# sch_AGV_Power.net
KiCad netlist of a schematic drawn in Altium Designer
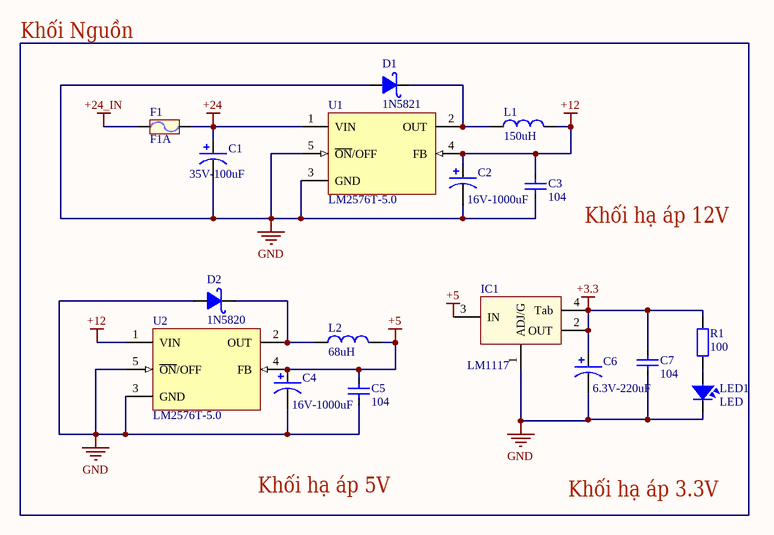
[diagram p0: sch_AGV_Power.SchDoc]

(export (version "E")
  (design (tool "Eeschema 10.0.6"))
  (components
    (comp (ref "C1")
      (value "35V-100uF")
      (footprint "CAP_D6.3")
      (description "Polarized Capacitor (Axial)")
      (fields (field (name "PUBLISHER") "Altium Limited"))
      (libsource (lib "schelib_AGVcontrol") (part "CapPol"))
    )
    (comp (ref "C2")
      (value "16V-1000uF")
      (footprint "CAP_D10")
      (description "Polarized Capacitor (Axial)")
      (fields (field (name "PUBLISHER") "Altium Limited"))
      (libsource (lib "schelib_AGVcontrol") (part "CapPol"))
    )
    (comp (ref "C3")
      (value "104")
      (footprint "CAP_0805")
      (description "Capacitor")
      (fields (field (name "PUBLISHER") "Altium Limited"))
      (libsource (lib "schelib_AGVcontrol") (part "CapSMD"))
    )
    (comp (ref "C4")
      (value "16V-1000uF")
      (footprint "CAP_D10")
      (description "Polarized Capacitor (Axial)")
      (fields (field (name "PUBLISHER") "Altium Limited"))
      (libsource (lib "schelib_AGVcontrol") (part "CapPol"))
    )
    (comp (ref "C5")
      (value "104")
      (footprint "CAP_0805")
      (description "Capacitor")
      (fields (field (name "PUBLISHER") "Altium Limited"))
      (libsource (lib "schelib_AGVcontrol") (part "CapSMD"))
    )
    (comp (ref "C6")
      (value "6.3V-220uF")
      (footprint "CAP_D10")
      (description "Polarized Capacitor (Axial)")
      (fields (field (name "PUBLISHER") "Altium Limited"))
      (libsource (lib "schelib_AGVcontrol") (part "CapPol"))
    )
    (comp (ref "C7")
      (value "104")
      (footprint "CAP_0805")
      (description "Capacitor")
      (fields (field (name "PUBLISHER") "Altium Limited"))
      (libsource (lib "schelib_AGVcontrol") (part "CapSMD"))
    )
    (comp (ref "D1")
      (value "1N5821")
      (footprint "SMA")
      (description "Schottky Rectifiers")
      (libsource (lib "schelib_AGVcontrol") (part "1N5822"))
    )
    (comp (ref "D2")
      (value "1N5820")
      (footprint "SMA")
      (description "Schottky Rectifiers")
      (libsource (lib "schelib_AGVcontrol") (part "1N5822"))
    )
    (comp (ref "F1")
      (value "F1A")
      (footprint "FUSE")
      (description "Fuse")
      (fields (field (name "DESIGNED BY") "VanDungEvn"))
      (libsource (lib "schelib_AGVcontrol") (part "Fuse"))
    )
    (comp (ref "IC1")
      (value "LM1117")
      (footprint "SOT223-4N")
      (description "3v3")
      (libsource (lib "schelib_AGVcontrol") (part "LM1117"))
    )
    (comp (ref "L1")
      (value "150uH")
      (footprint "L-SMD-M-12x10")
      (description "Inductor")
      (libsource (lib "schelib_AGVcontrol") (part "Inductor"))
    )
    (comp (ref "L2")
      (value "68uH")
      (footprint "L-SMD-M-12x10")
      (description "Inductor")
      (libsource (lib "schelib_AGVcontrol") (part "Inductor"))
    )
    (comp (ref "LED1")
      (value "LED")
      (footprint "LED_BLUE_SMD_0805")
      (description "LED Single colour Green and Red")
      (libsource (lib "schelib_AGVcontrol") (part "LED"))
    )
    (comp (ref "R1")
      (value "100")
      (footprint "RES_SMD_0805")
      (description "Resistor")
      (fields
        (field (name "MANUFACTURER") "Generic Components")
        (field (name "PUBLISHER") "Altium Hobart Technology Centre")
      )
      (libsource (lib "schelib_AGVcontrol") (part "Res"))
    )
    (comp (ref "U1")
      (value "LM2576T-5.0")
      (footprint "TO-263")
      (description "SIMPLE SWITCHER; 3A Step-Down Voltage Regulator")
      (fields
        (field (name "MANUFACTURER") "National Semiconductor")
        (field (name "DIGIKEYPARTNUMBER") "LM2576T-5.0-ND")
        (field (name "PUBLISHER") "Altium Limited")
      )
      (libsource (lib "schelib_AGVcontrol") (part "LM2576T-5.0"))
    )
    (comp (ref "U2")
      (value "LM2576T-5.0")
      (footprint "TO-263")
      (description "SIMPLE SWITCHER; 3A Step-Down Voltage Regulator")
      (fields
        (field (name "MANUFACTURER") "National Semiconductor")
        (field (name "DIGIKEYPARTNUMBER") "LM2576T-5.0-ND")
        (field (name "PUBLISHER") "Altium Limited")
      )
      (libsource (lib "schelib_AGVcontrol") (part "LM2576T-5.0"))
    )
  )
  (nets
    (net (code "1") (name "+3.3") (class "Default")
      (node (ref "C6") (pin "1") (pinfunction "1_1") (pintype "passive"))
      (node (ref "C7") (pin "2") (pinfunction "2_2") (pintype "passive"))
      (node (ref "IC1") (pin "2") (pinfunction "OUT_2") (pintype "passive"))
      (node (ref "IC1") (pin "4") (pinfunction "Tab_4") (pintype "passive"))
      (node (ref "R1") (pin "1") (pinfunction "1_1") (pintype "passive"))
    )
    (net (code "2") (name "+5") (class "Default")
      (node (ref "C4") (pin "1") (pinfunction "1_1") (pintype "passive"))
      (node (ref "C5") (pin "2") (pinfunction "2_2") (pintype "passive"))
      (node (ref "IC1") (pin "3") (pinfunction "IN_3") (pintype "passive"))
      (node (ref "L2") (pin "2") (pinfunction "2_2") (pintype "passive"))
      (node (ref "U2") (pin "4") (pinfunction "FB_4") (pintype "input"))
    )
    (net (code "3") (name "+12") (class "Default")
      (node (ref "C2") (pin "1") (pinfunction "1_1") (pintype "passive"))
      (node (ref "C3") (pin "2") (pinfunction "2_2") (pintype "passive"))
      (node (ref "L1") (pin "2") (pinfunction "2_2") (pintype "passive"))
      (node (ref "U1") (pin "4") (pinfunction "FB_4") (pintype "input"))
      (node (ref "U2") (pin "1") (pinfunction "VIN_1") (pintype "power_in"))
    )
    (net (code "4") (name "+24") (class "Default")
      (node (ref "C1") (pin "1") (pinfunction "1_1") (pintype "passive"))
      (node (ref "F1") (pin "1") (pinfunction "1_1") (pintype "passive"))
      (node (ref "U1") (pin "1") (pinfunction "VIN_1") (pintype "power_in"))
    )
    (net (code "5") (name "+24_IN") (class "Default")
      (node (ref "F1") (pin "2") (pinfunction "2_2") (pintype "passive"))
    )
    (net (code "6") (name "GND") (class "Default")
      (node (ref "C1") (pin "2") (pinfunction "2_2") (pintype "passive"))
      (node (ref "C2") (pin "2") (pinfunction "2_2") (pintype "passive"))
      (node (ref "C3") (pin "1") (pinfunction "1_1") (pintype "passive"))
      (node (ref "C4") (pin "2") (pinfunction "2_2") (pintype "passive"))
      (node (ref "C5") (pin "1") (pinfunction "1_1") (pintype "passive"))
      (node (ref "C6") (pin "2") (pinfunction "2_2") (pintype "passive"))
      (node (ref "C7") (pin "1") (pinfunction "1_1") (pintype "passive"))
      (node (ref "D1") (pin "1") (pinfunction "A_1") (pintype "passive"))
      (node (ref "D2") (pin "1") (pinfunction "A_1") (pintype "passive"))
      (node (ref "IC1") (pin "1") (pinfunction "ADJ/G_1") (pintype "passive"))
      (node (ref "LED1") (pin "2") (pinfunction "2_2") (pintype "passive"))
      (node (ref "U1") (pin "3") (pinfunction "GND_3") (pintype "power_in"))
      (node (ref "U1") (pin "5") (pinfunction "~{ON}/OFF_5") (pintype "input"))
      (node (ref "U2") (pin "3") (pinfunction "GND_3") (pintype "power_in"))
      (node (ref "U2") (pin "5") (pinfunction "~{ON}/OFF_5") (pintype "input"))
    )
    (net (code "7") (name "Net-(D1-K)") (class "Default")
      (node (ref "D1") (pin "2") (pinfunction "K_2") (pintype "passive"))
      (node (ref "L1") (pin "1") (pinfunction "1_1") (pintype "passive"))
      (node (ref "U1") (pin "2") (pinfunction "OUT_2") (pintype "power_in"))
    )
    (net (code "8") (name "Net-(D2-K)") (class "Default")
      (node (ref "D2") (pin "2") (pinfunction "K_2") (pintype "passive"))
      (node (ref "L2") (pin "1") (pinfunction "1_1") (pintype "passive"))
      (node (ref "U2") (pin "2") (pinfunction "OUT_2") (pintype "power_in"))
    )
    (net (code "9") (name "Net-(LED1-Pad1)") (class "Default")
      (node (ref "LED1") (pin "1") (pinfunction "1_1") (pintype "passive"))
      (node (ref "R1") (pin "2") (pinfunction "2_2") (pintype "passive"))
    )
  )
)
